# connector_board.net
KiCad netlist of a schematic drawn in EAGLE
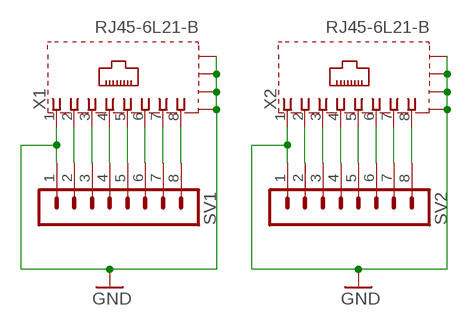
[diagram p0: schematic, sheet 1]

(export (version "E")
  (design (tool "Eeschema 10.0.6"))
  (components
    (comp (ref "SV1")
      (value "MA08-1")
      (footprint "eagle-import:MA08-1")
      (libsource (lib "eagle-import") (part "MA08-1"))
    )
    (comp (ref "SV2")
      (value "MA08-1")
      (footprint "eagle-import:MA08-1")
      (libsource (lib "eagle-import") (part "MA08-1"))
    )
    (comp (ref "X1")
      (value "RJ45-6L21-B")
      (footprint "eagle-import:RJ45-SHIELD1")
      (libsource (lib "eagle-import") (part "RJ4521-B-6L"))
    )
    (comp (ref "X2")
      (value "RJ45-6L21-B")
      (footprint "eagle-import:RJ45-SHIELD1")
      (libsource (lib "eagle-import") (part "RJ4521-B-6L"))
    )
  )
  (nets
    (net (code "1") (name "GND") (class "Default")
      (node (ref "SV1") (pin "1") (pinfunction "1_1") (pintype "passive"))
      (node (ref "SV2") (pin "1") (pinfunction "1_1") (pintype "passive"))
      (node (ref "X1") (pin "1") (pinfunction "1_1") (pintype "passive"))
      (node (ref "X1") (pin "S1") (pinfunction "S_S1") (pintype "passive"))
      (node (ref "X1") (pin "S2") (pinfunction "S_S2") (pintype "passive"))
      (node (ref "X1") (pin "S3") (pinfunction "S_S3") (pintype "passive"))
      (node (ref "X1") (pin "S4") (pinfunction "S_S4") (pintype "passive"))
      (node (ref "X2") (pin "1") (pinfunction "1_1") (pintype "passive"))
      (node (ref "X2") (pin "S1") (pinfunction "S_S1") (pintype "passive"))
      (node (ref "X2") (pin "S2") (pinfunction "S_S2") (pintype "passive"))
      (node (ref "X2") (pin "S3") (pinfunction "S_S3") (pintype "passive"))
      (node (ref "X2") (pin "S4") (pinfunction "S_S4") (pintype "passive"))
    )
    (net (code "2") (name "Net-(SV1-Pad2)") (class "Default")
      (node (ref "SV1") (pin "2") (pinfunction "2_2") (pintype "passive"))
      (node (ref "X1") (pin "2") (pinfunction "2_2") (pintype "passive"))
    )
    (net (code "3") (name "Net-(SV1-Pad3)") (class "Default")
      (node (ref "SV1") (pin "3") (pinfunction "3_3") (pintype "passive"))
      (node (ref "X1") (pin "3") (pinfunction "3_3") (pintype "passive"))
    )
    (net (code "4") (name "Net-(SV1-Pad4)") (class "Default")
      (node (ref "SV1") (pin "4") (pinfunction "4_4") (pintype "passive"))
      (node (ref "X1") (pin "4") (pinfunction "4_4") (pintype "passive"))
    )
    (net (code "5") (name "Net-(SV1-Pad5)") (class "Default")
      (node (ref "SV1") (pin "5") (pinfunction "5_5") (pintype "passive"))
      (node (ref "X1") (pin "5") (pinfunction "5_5") (pintype "passive"))
    )
    (net (code "6") (name "Net-(SV1-Pad6)") (class "Default")
      (node (ref "SV1") (pin "6") (pinfunction "6_6") (pintype "passive"))
      (node (ref "X1") (pin "6") (pinfunction "6_6") (pintype "passive"))
    )
    (net (code "7") (name "Net-(SV1-Pad7)") (class "Default")
      (node (ref "SV1") (pin "7") (pinfunction "7_7") (pintype "passive"))
      (node (ref "X1") (pin "7") (pinfunction "7_7") (pintype "passive"))
    )
    (net (code "8") (name "Net-(SV1-Pad8)") (class "Default")
      (node (ref "SV1") (pin "8") (pinfunction "8_8") (pintype "passive"))
      (node (ref "X1") (pin "8") (pinfunction "8_8") (pintype "passive"))
    )
    (net (code "9") (name "Net-(SV2-Pad2)") (class "Default")
      (node (ref "SV2") (pin "2") (pinfunction "2_2") (pintype "passive"))
      (node (ref "X2") (pin "2") (pinfunction "2_2") (pintype "passive"))
    )
    (net (code "10") (name "Net-(SV2-Pad3)") (class "Default")
      (node (ref "SV2") (pin "3") (pinfunction "3_3") (pintype "passive"))
      (node (ref "X2") (pin "3") (pinfunction "3_3") (pintype "passive"))
    )
    (net (code "11") (name "Net-(SV2-Pad4)") (class "Default")
      (node (ref "SV2") (pin "4") (pinfunction "4_4") (pintype "passive"))
      (node (ref "X2") (pin "4") (pinfunction "4_4") (pintype "passive"))
    )
    (net (code "12") (name "Net-(SV2-Pad5)") (class "Default")
      (node (ref "SV2") (pin "5") (pinfunction "5_5") (pintype "passive"))
      (node (ref "X2") (pin "5") (pinfunction "5_5") (pintype "passive"))
    )
    (net (code "13") (name "Net-(SV2-Pad6)") (class "Default")
      (node (ref "SV2") (pin "6") (pinfunction "6_6") (pintype "passive"))
      (node (ref "X2") (pin "6") (pinfunction "6_6") (pintype "passive"))
    )
    (net (code "14") (name "Net-(SV2-Pad7)") (class "Default")
      (node (ref "SV2") (pin "7") (pinfunction "7_7") (pintype "passive"))
      (node (ref "X2") (pin "7") (pinfunction "7_7") (pintype "passive"))
    )
    (net (code "15") (name "Net-(SV2-Pad8)") (class "Default")
      (node (ref "SV2") (pin "8") (pinfunction "8_8") (pintype "passive"))
      (node (ref "X2") (pin "8") (pinfunction "8_8") (pintype "passive"))
    )
  )
)
